# RC_Car_SCH.net
KiCad netlist of a schematic drawn in Altium Designer
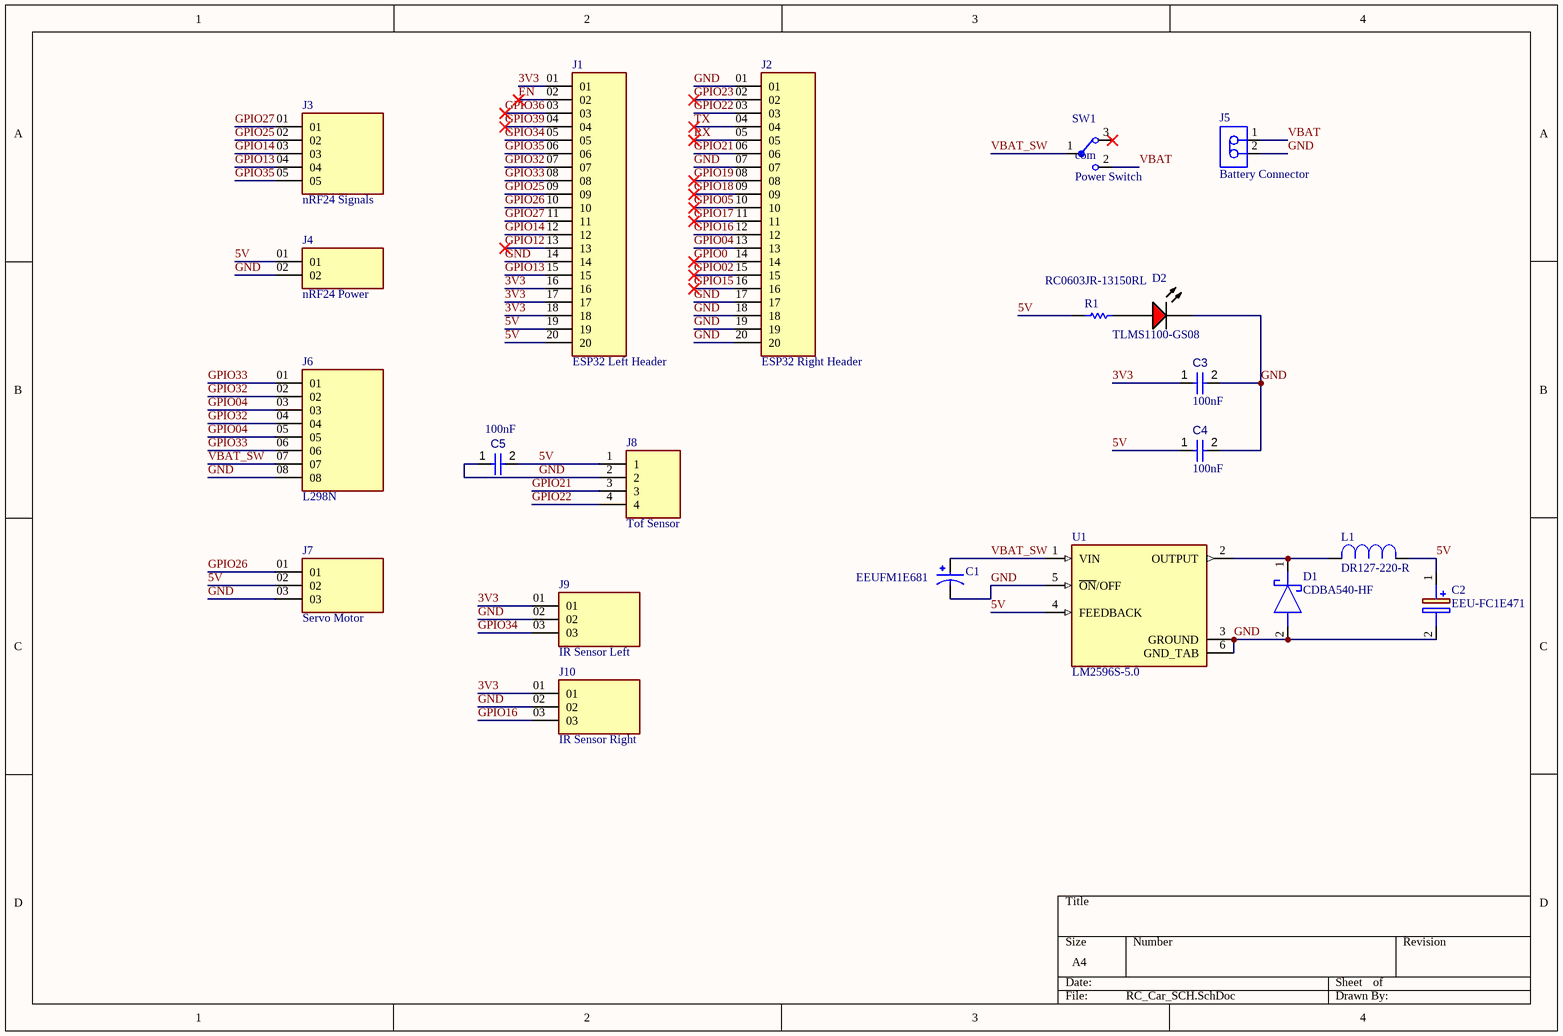
[diagram p0: RC_Car_SCH.SchDoc]

(export (version "E")
  (design (tool "Eeschema 10.0.6"))
  (components
    (comp (ref "C1")
      (value "EEUFM1E681")
      (footprint "CAPPRD500W60D1000H2000")
      (description "680F 25V Aluminum Electrolytic Capacitors Radial, Can 5000 Hrs @ 105C")
      (fields (field (name "MF") "Panasonic") (field (name "DIGI-KEY_PART_NUMBER") "P12390-ND"))
      (libsource (lib "EEUFM1E681") (part "EEUFM1E681"))
    )
    (comp (ref "C2")
      (value "EEU-FC1E471")
      (footprint "SamacSys:CAPPRD350W65D815H2200")
      (description "Capacitor Polarised")
      (fields (field (name "MOUSER PART NUMBER") "667-EEU-FC1E471"))
      (libsource (lib "*") (part "EEU-FC1E471"))
    )
    (comp (ref "C3")
      (value "100nF")
      (footprint "CAPC1608X90X40NL10T20")
      (description "Chip Capacitor, 100 nF, +/- 10%, 50 V, 0603 (1608 Metric)")
      (fields (field (name "TOLERANCE") "10%") (field (name "Comment") "Capacitor 100 nF +/-10% 50 V 0603"))
      (libsource (lib "Shubh Patel") (part "CAP-NP-2"))
    )
    (comp (ref "C4")
      (value "100nF")
      (footprint "CAPC1608X90X40NL10T20")
      (description "Chip Capacitor, 100 nF, +/- 10%, 50 V, 0603 (1608 Metric)")
      (fields (field (name "TOLERANCE") "10%") (field (name "Comment") "Capacitor 100 nF +/-10% 50 V 0603"))
      (libsource (lib "Shubh Patel") (part "CAP-NP-2"))
    )
    (comp (ref "C5")
      (value "100nF")
      (footprint "CAPC1608X90X40NL10T20")
      (description "Chip Capacitor, 100 nF, +/- 10%, 50 V, 0603 (1608 Metric)")
      (fields (field (name "TOLERANCE") "10%") (field (name "Comment") "Capacitor 100 nF +/-10% 50 V 0603"))
      (libsource (lib "Shubh Patel") (part "CAP-NP-2"))
    )
    (comp (ref "D1")
      (value "CDBA540-HF")
      (footprint "SamacSys:DIOM5225X250N")
      (description "Schottky Diode")
      (fields (field (name "MOUSER PART NUMBER") "750-CDBA540-HF"))
      (libsource (lib "*") (part "CDBA540-HF"))
    )
    (comp (ref "D2")
      (value "TLMS1100-GS08")
      (footprint "VISH-TLMX1100_V")
      (description "Red Led, 20mA, 2.1 V, -40 to 100 degC, 2-Pin SMD (0603), RoHS, Tape and Reel")
      (fields (field (name "MANUFACTURER") "Vishay Semiconductor") (field (name "POWER") "90mW"))
      (libsource (lib "Shubh Patel") (part "LED-RED-AK-2"))
    )
    (comp (ref "J1")
      (value "ESP32 Left Header")
      (footprint "SAMTEC_SSQ-120-XX-X-S")
      (description "20 Position Receptacle Connector 0.100 (2.54mm) Through Hole Gold")
      (fields (field (name "MF") "Samtec") (field (name "MP") "SSQ-120-22-F-S"))
      (libsource (lib "SSQ-120-XX-X-S") (part "SSQ-120-XX-X-S"))
    )
    (comp (ref "J2")
      (value "ESP32 Right Header")
      (footprint "SAMTEC_SSQ-120-XX-X-S")
      (description "20 Position Receptacle Connector 0.100 (2.54mm) Through Hole Gold")
      (fields (field (name "MF") "Samtec") (field (name "MP") "SSQ-120-22-F-S"))
      (libsource (lib "SSQ-120-XX-X-S") (part "SSQ-120-XX-X-S"))
    )
    (comp (ref "J3")
      (value "nRF24 Signals")
      (footprint "SAMTEC_SSQ-105-02-T-S")
      (description "Headers & Wire Housings .100 Tiger Buy Socket Strip, Square Tail")
      (fields (field (name "MF") "Samtec") (field (name "MP") "SSQ-105-02-T-S"))
      (libsource (lib "SSQ-105-02-T-S") (part "SSQ-105-02-T-S"))
    )
    (comp (ref "J4")
      (value "nRF24 Power")
      (footprint "SAMTEC_SSQ-102-02-T-S")
      (description "SSQ Series .100 Tiger Buyâ„¢ Socket Strip, Square Tail")
      (fields (field (name "MF") "Samtec Inc.") (field (name "MP") "SSQ-102-02-T-S"))
      (libsource (lib "SSQ-102-02-T-S") (part "SSQ-102-02-T-S"))
    )
    (comp (ref "J5")
      (value "Battery Connector")
      (footprint "JST-B2B-PH-K-S_V")
      (fields (field (name "MANUFACTURER") "JST"))
      (libsource (lib "Altium Content Vault") (part "CN-2P-F-QF2"))
    )
    (comp (ref "J6")
      (value "L298N")
      (footprint "SAMTEC_SSQ-108-02-T-S")
      (description "Headers & Wire Housings .100 Tiger Buy Socket Strip, Square Tail")
      (fields (field (name "MF") "Samtec") (field (name "MP") "SSQ-108-02-T-S"))
      (libsource (lib "SSQ-108-02-T-S") (part "SSQ-108-02-T-S"))
    )
    (comp (ref "J7")
      (value "Servo Motor")
      (footprint "SAMTEC_SSQ-103-02-T-S")
      (description "3 Position Receptacle Connector 0.100 (2.54mm) Through Hole, Right Angle Tin")
      (fields (field (name "MF") "Samtec") (field (name "MP") "SSQ-103-02-T-S"))
      (libsource (lib "SSQ-103-02-T-S") (part "SSQ-103-02-T-S"))
    )
    (comp (ref "J8")
      (value "Tof Sensor")
      (footprint "SamacSys:SAMTEC_SSQ-104-02-T-S")
      (description "Connector")
      (fields (field (name "MANUFACTURER_PART_NUMBER") "SSQ-104-02-T-S"))
      (libsource (lib "*") (part "SSQ-104-02-T-S"))
    )
    (comp (ref "J9")
      (value "IR Sensor Left")
      (footprint "SAMTEC_SSQ-103-02-T-S")
      (description "3 Position Receptacle Connector 0.100 (2.54mm) Through Hole, Right Angle Tin")
      (fields (field (name "MF") "Samtec") (field (name "MP") "SSQ-103-02-T-S"))
      (libsource (lib "SSQ-103-02-T-S") (part "SSQ-103-02-T-S"))
    )
    (comp (ref "J10")
      (value "IR Sensor Right")
      (footprint "SAMTEC_SSQ-103-02-T-S")
      (description "3 Position Receptacle Connector 0.100 (2.54mm) Through Hole, Right Angle Tin")
      (fields (field (name "MF") "Samtec") (field (name "MP") "SSQ-103-02-T-S"))
      (libsource (lib "SSQ-103-02-T-S") (part "SSQ-103-02-T-S"))
    )
    (comp (ref "L1")
      (value "DR127-220-R")
      (footprint "INDM125125X800N")
      (description "22ÂµH Shielded Wirewound Inductor 4A 39.1mOhm Nonstandard")
      (fields (field (name "MF") "Eaton") (field (name "DIGI-KEY_PART_NUMBER") "513-1044-1-ND"))
      (libsource (lib "DR127-220-R") (part "DR127-220-R"))
    )
    (comp (ref "R1")
      (value "RC0603JR-13150RL")
      (footprint "RESC1608X55X25ML10T15")
      (fields (field (name "MANUFACTURER") "Yageo"))
      (libsource (lib "Altium Content Vault") (part "RES"))
    )
    (comp (ref "SW1")
      (value "Power Switch")
      (footprint "450301014042")
      (fields
        (field (name "MF") "{'manufacturer': u'~{W}xfcrth Elektronik'}")
        (field (name "MP") "450301014042")
      )
      (libsource (lib "450301014042") (part "450301014042"))
    )
    (comp (ref "U1")
      (value "LM2596S-5.0")
      (footprint "TO170P1524X483-6N")
      (description "SIMPLE SWITCHERÂ® 4.5V to 40V, 3A Low Component Count Step-Down Regulator")
      (fields (field (name "MF") "Texas Instruments") (field (name "MP") "LM2596S-5.0/NOPB"))
      (libsource (lib "LM2596S-5.0") (part "LM2596S-5.0"))
    )
  )
  (nets
    (net (code "1") (name "/3V3") (class "Default")
      (node (ref "C3") (pin "1") (pinfunction "1_1") (pintype "passive"))
      (node (ref "J1") (pin "01") (pinfunction "01_01") (pintype "passive"))
      (node (ref "J1") (pin "16") (pinfunction "16_16") (pintype "passive"))
      (node (ref "J1") (pin "17") (pinfunction "17_17") (pintype "passive"))
      (node (ref "J1") (pin "18") (pinfunction "18_18") (pintype "passive"))
      (node (ref "J10") (pin "01") (pinfunction "01_01") (pintype "passive"))
      (node (ref "J9") (pin "01") (pinfunction "01_01") (pintype "passive"))
    )
    (net (code "2") (name "/5V") (class "Default")
      (node (ref "C2") (pin "1") (pinfunction "+_1") (pintype "passive"))
      (node (ref "C4") (pin "1") (pinfunction "1_1") (pintype "passive"))
      (node (ref "C5") (pin "2") (pinfunction "2_2") (pintype "passive"))
      (node (ref "J1") (pin "19") (pinfunction "19_19") (pintype "passive"))
      (node (ref "J1") (pin "20") (pinfunction "20_20") (pintype "passive"))
      (node (ref "J4") (pin "01") (pinfunction "01_01") (pintype "passive"))
      (node (ref "J7") (pin "02") (pinfunction "02_02") (pintype "passive"))
      (node (ref "J8") (pin "1") (pinfunction "1_1") (pintype "passive"))
      (node (ref "L1") (pin "1") (pinfunction "1_1") (pintype "passive"))
      (node (ref "R1") (pin "1") (pinfunction "1_1") (pintype "passive"))
      (node (ref "U1") (pin "4") (pinfunction "FEEDBACK_4") (pintype "input"))
    )
    (net (code "3") (name "/EN") (class "Default")
      (node (ref "J1") (pin "02") (pinfunction "02_02") (pintype "passive+no_connect"))
    )
    (net (code "4") (name "/GND") (class "Default")
      (node (ref "C1") (pin "N") (pinfunction "N_N") (pintype "passive"))
      (node (ref "C2") (pin "2") (pinfunction "-_2") (pintype "passive"))
      (node (ref "C3") (pin "2") (pinfunction "2_2") (pintype "passive"))
      (node (ref "C4") (pin "2") (pinfunction "2_2") (pintype "passive"))
      (node (ref "C5") (pin "1") (pinfunction "1_1") (pintype "passive"))
      (node (ref "D1") (pin "2") (pinfunction "A_2") (pintype "passive"))
      (node (ref "D2") (pin "2") (pinfunction "K_2") (pintype "passive"))
      (node (ref "J1") (pin "14") (pinfunction "14_14") (pintype "passive"))
      (node (ref "J10") (pin "02") (pinfunction "02_02") (pintype "passive"))
      (node (ref "J2") (pin "01") (pinfunction "01_01") (pintype "passive"))
      (node (ref "J2") (pin "07") (pinfunction "07_07") (pintype "passive"))
      (node (ref "J2") (pin "17") (pinfunction "17_17") (pintype "passive"))
      (node (ref "J2") (pin "18") (pinfunction "18_18") (pintype "passive"))
      (node (ref "J2") (pin "19") (pinfunction "19_19") (pintype "passive"))
      (node (ref "J2") (pin "20") (pinfunction "20_20") (pintype "passive"))
      (node (ref "J4") (pin "02") (pinfunction "02_02") (pintype "passive"))
      (node (ref "J5") (pin "2") (pinfunction "2_2") (pintype "passive"))
      (node (ref "J6") (pin "08") (pinfunction "08_08") (pintype "passive"))
      (node (ref "J7") (pin "03") (pinfunction "03_03") (pintype "passive"))
      (node (ref "J8") (pin "2") (pinfunction "2_2") (pintype "passive"))
      (node (ref "J9") (pin "02") (pinfunction "02_02") (pintype "passive"))
      (node (ref "U1") (pin "3") (pinfunction "GROUND_3") (pintype "power_in"))
      (node (ref "U1") (pin "5") (pinfunction "~{ON}/OFF_5") (pintype "input"))
      (node (ref "U1") (pin "6") (pinfunction "GND_TAB_6") (pintype "power_in"))
    )
    (net (code "5") (name "/GPIO0") (class "Default")
      (node (ref "J2") (pin "14") (pinfunction "14_14") (pintype "passive+no_connect"))
    )
    (net (code "6") (name "/GPIO02") (class "Default")
      (node (ref "J2") (pin "15") (pinfunction "15_15") (pintype "passive+no_connect"))
    )
    (net (code "7") (name "/GPIO04") (class "Default")
      (node (ref "J2") (pin "13") (pinfunction "13_13") (pintype "passive"))
      (node (ref "J6") (pin "03") (pinfunction "03_03") (pintype "passive"))
      (node (ref "J6") (pin "05") (pinfunction "05_05") (pintype "passive"))
    )
    (net (code "8") (name "/GPIO05") (class "Default")
      (node (ref "J2") (pin "10") (pinfunction "10_10") (pintype "passive+no_connect"))
    )
    (net (code "9") (name "/GPIO12") (class "Default")
      (node (ref "J1") (pin "13") (pinfunction "13_13") (pintype "passive+no_connect"))
    )
    (net (code "10") (name "/GPIO13") (class "Default")
      (node (ref "J1") (pin "15") (pinfunction "15_15") (pintype "passive"))
      (node (ref "J3") (pin "04") (pinfunction "04_04") (pintype "passive"))
    )
    (net (code "11") (name "/GPIO14") (class "Default")
      (node (ref "J1") (pin "12") (pinfunction "12_12") (pintype "passive"))
      (node (ref "J3") (pin "03") (pinfunction "03_03") (pintype "passive"))
    )
    (net (code "12") (name "/GPIO15") (class "Default")
      (node (ref "J2") (pin "16") (pinfunction "16_16") (pintype "passive+no_connect"))
    )
    (net (code "13") (name "/GPIO16") (class "Default")
      (node (ref "J10") (pin "03") (pinfunction "03_03") (pintype "passive"))
      (node (ref "J2") (pin "12") (pinfunction "12_12") (pintype "passive"))
    )
    (net (code "14") (name "/GPIO17") (class "Default")
      (node (ref "J2") (pin "11") (pinfunction "11_11") (pintype "passive+no_connect"))
    )
    (net (code "15") (name "/GPIO18") (class "Default")
      (node (ref "J2") (pin "09") (pinfunction "09_09") (pintype "passive+no_connect"))
    )
    (net (code "16") (name "/GPIO19") (class "Default")
      (node (ref "J2") (pin "08") (pinfunction "08_08") (pintype "passive+no_connect"))
    )
    (net (code "17") (name "/GPIO21") (class "Default")
      (node (ref "J2") (pin "06") (pinfunction "06_06") (pintype "passive"))
      (node (ref "J8") (pin "3") (pinfunction "3_3") (pintype "passive"))
    )
    (net (code "18") (name "/GPIO22") (class "Default")
      (node (ref "J2") (pin "03") (pinfunction "03_03") (pintype "passive"))
      (node (ref "J8") (pin "4") (pinfunction "4_4") (pintype "passive"))
    )
    (net (code "19") (name "/GPIO23") (class "Default")
      (node (ref "J2") (pin "02") (pinfunction "02_02") (pintype "passive+no_connect"))
    )
    (net (code "20") (name "/GPIO25") (class "Default")
      (node (ref "J1") (pin "09") (pinfunction "09_09") (pintype "passive"))
      (node (ref "J3") (pin "02") (pinfunction "02_02") (pintype "passive"))
    )
    (net (code "21") (name "/GPIO26") (class "Default")
      (node (ref "J1") (pin "10") (pinfunction "10_10") (pintype "passive"))
      (node (ref "J7") (pin "01") (pinfunction "01_01") (pintype "passive"))
    )
    (net (code "22") (name "/GPIO27") (class "Default")
      (node (ref "J1") (pin "11") (pinfunction "11_11") (pintype "passive"))
      (node (ref "J3") (pin "01") (pinfunction "01_01") (pintype "passive"))
    )
    (net (code "23") (name "/GPIO32") (class "Default")
      (node (ref "J1") (pin "07") (pinfunction "07_07") (pintype "passive"))
      (node (ref "J6") (pin "02") (pinfunction "02_02") (pintype "passive"))
      (node (ref "J6") (pin "04") (pinfunction "04_04") (pintype "passive"))
    )
    (net (code "24") (name "/GPIO33") (class "Default")
      (node (ref "J1") (pin "08") (pinfunction "08_08") (pintype "passive"))
      (node (ref "J6") (pin "01") (pinfunction "01_01") (pintype "passive"))
      (node (ref "J6") (pin "06") (pinfunction "06_06") (pintype "passive"))
    )
    (net (code "25") (name "/GPIO34") (class "Default")
      (node (ref "J1") (pin "05") (pinfunction "05_05") (pintype "passive"))
      (node (ref "J9") (pin "03") (pinfunction "03_03") (pintype "passive"))
    )
    (net (code "26") (name "/GPIO35") (class "Default")
      (node (ref "J1") (pin "06") (pinfunction "06_06") (pintype "passive"))
      (node (ref "J3") (pin "05") (pinfunction "05_05") (pintype "passive"))
    )
    (net (code "27") (name "/GPIO36") (class "Default")
      (node (ref "J1") (pin "03") (pinfunction "03_03") (pintype "passive+no_connect"))
    )
    (net (code "28") (name "/GPIO39") (class "Default")
      (node (ref "J1") (pin "04") (pinfunction "04_04") (pintype "passive+no_connect"))
    )
    (net (code "29") (name "/RX") (class "Default")
      (node (ref "J2") (pin "05") (pinfunction "05_05") (pintype "passive+no_connect"))
    )
    (net (code "30") (name "/TX") (class "Default")
      (node (ref "J2") (pin "04") (pinfunction "04_04") (pintype "passive+no_connect"))
    )
    (net (code "31") (name "/VBAT") (class "Default")
      (node (ref "J5") (pin "1") (pinfunction "1_1") (pintype "passive"))
      (node (ref "SW1") (pin "2") (pinfunction "2_2") (pintype "passive"))
    )
    (net (code "32") (name "/VBAT_SW") (class "Default")
      (node (ref "C1") (pin "P") (pinfunction "P_P") (pintype "passive"))
      (node (ref "J6") (pin "07") (pinfunction "07_07") (pintype "passive"))
      (node (ref "SW1") (pin "1") (pinfunction "1_1") (pintype "passive"))
      (node (ref "U1") (pin "1") (pinfunction "VIN_1") (pintype "input"))
    )
    (net (code "33") (name "Net-(D1-K)") (class "Default")
      (node (ref "D1") (pin "1") (pinfunction "K_1") (pintype "passive"))
      (node (ref "L1") (pin "2") (pinfunction "2_2") (pintype "passive"))
      (node (ref "U1") (pin "2") (pinfunction "OUTPUT_2") (pintype "output"))
    )
    (net (code "34") (name "Net-(D2-A)") (class "Default")
      (node (ref "D2") (pin "1") (pinfunction "A_1") (pintype "passive"))
      (node (ref "R1") (pin "2") (pinfunction "2_2") (pintype "passive"))
    )
    (net (code "35") (name "unconnected-(SW1-Pad3)") (class "Default")
      (node (ref "SW1") (pin "3") (pinfunction "3_3") (pintype "passive+no_connect"))
    )
  )
)
